# DiodeLadderFilter.net
KiCad netlist of a schematic drawn in Altium Designer
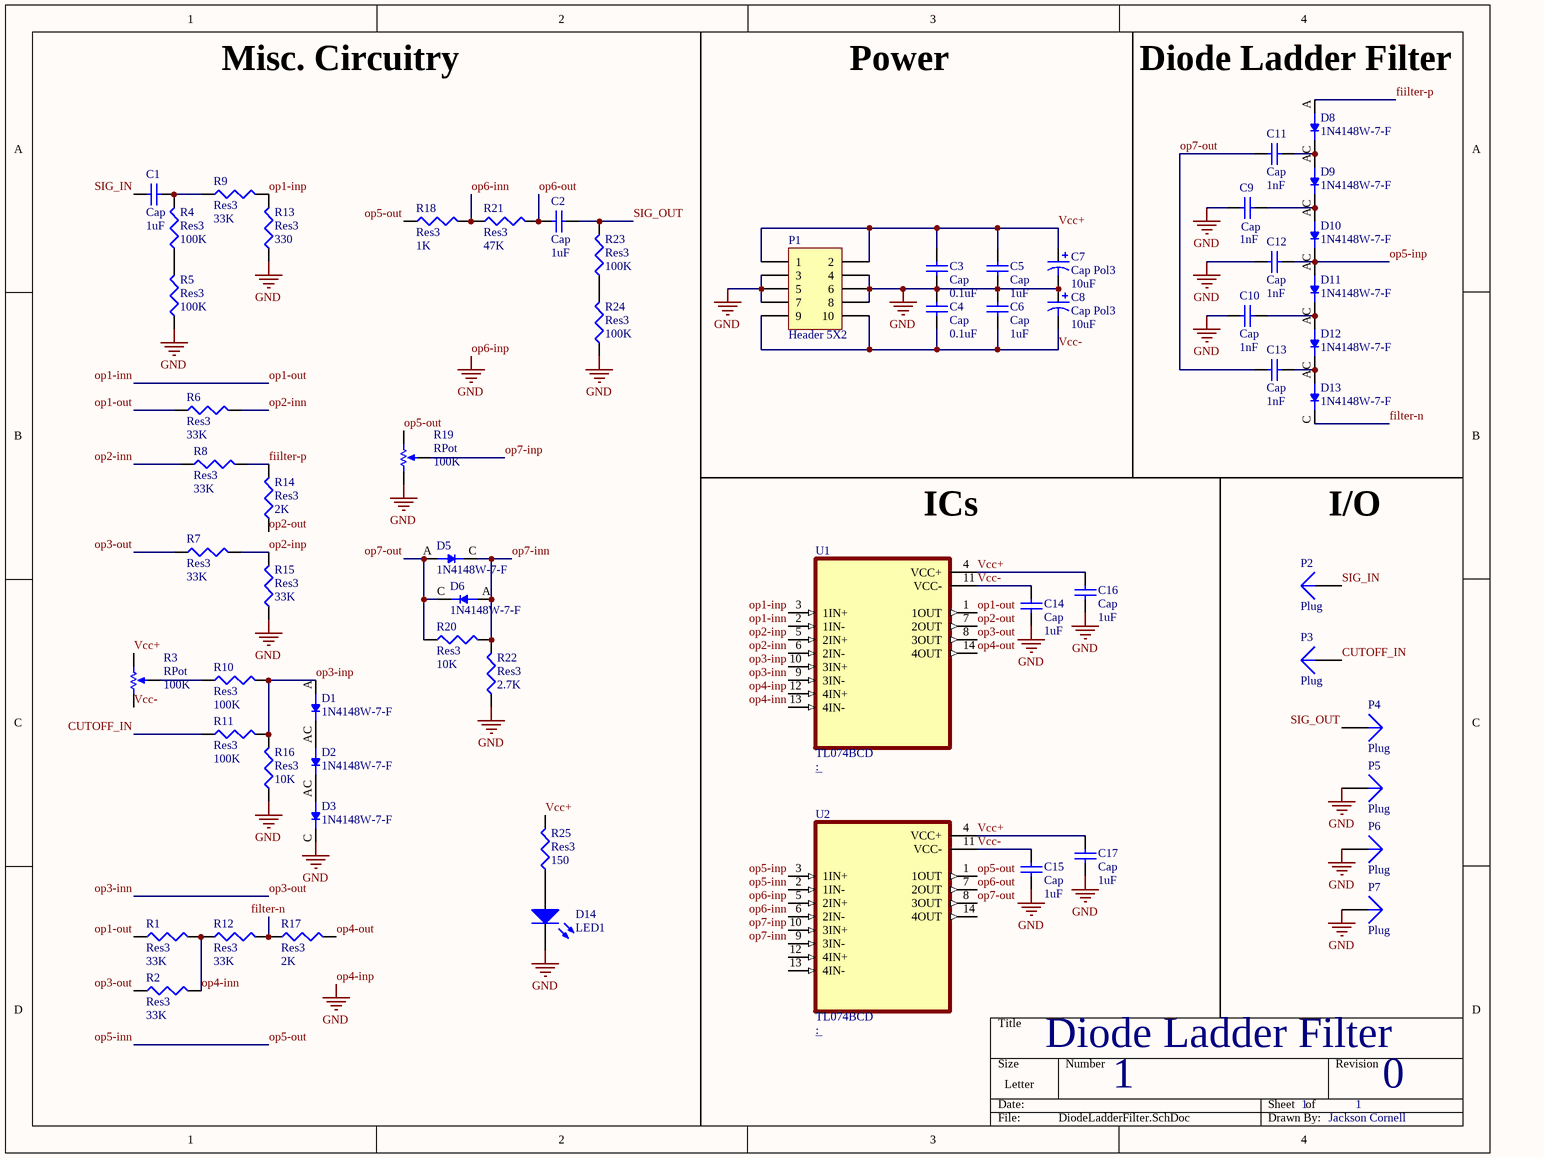
[diagram p0: DiodeLadderFilter.SchDoc]

(export (version "E")
  (design (tool "Eeschema 10.0.6"))
  (components
    (comp (ref "C1")
      (value "Cap")
      (footprint "CAPC1608X90")
      (description "Capacitor")
      (fields (field (name "ALTIUM_VALUE") "1uF") (field (name "PUBLISHER") "Altium Limited"))
      (libsource (lib "Miscellaneous Devices") (part "Cap"))
    )
    (comp (ref "C2")
      (value "Cap")
      (footprint "CAPC1608X90")
      (description "Capacitor")
      (fields (field (name "ALTIUM_VALUE") "1uF") (field (name "PUBLISHER") "Altium Limited"))
      (libsource (lib "Miscellaneous Devices") (part "Cap"))
    )
    (comp (ref "C3")
      (value "Cap")
      (footprint "CAPC1608X90")
      (description "Capacitor")
      (fields (field (name "ALTIUM_VALUE") "0.1uF") (field (name "PUBLISHER") "Altium Limited"))
      (libsource (lib "Miscellaneous Devices") (part "Cap"))
    )
    (comp (ref "C4")
      (value "Cap")
      (footprint "CAPC1608X90")
      (description "Capacitor")
      (fields (field (name "ALTIUM_VALUE") "0.1uF") (field (name "PUBLISHER") "Altium Limited"))
      (libsource (lib "Miscellaneous Devices") (part "Cap"))
    )
    (comp (ref "C5")
      (value "Cap")
      (footprint "CAPC1608X90")
      (description "Capacitor")
      (fields (field (name "ALTIUM_VALUE") "1uF") (field (name "PUBLISHER") "Altium Limited"))
      (libsource (lib "Miscellaneous Devices") (part "Cap"))
    )
    (comp (ref "C6")
      (value "Cap")
      (footprint "CAPC1608X90")
      (description "Capacitor")
      (fields (field (name "ALTIUM_VALUE") "1uF") (field (name "PUBLISHER") "Altium Limited"))
      (libsource (lib "Miscellaneous Devices") (part "Cap"))
    )
    (comp (ref "C7")
      (value "Cap Pol3")
      (footprint "2220")
      (description "Polarized Capacitor (Surface Mount)")
      (fields (field (name "ALTIUM_VALUE") "10uF") (field (name "PUBLISHER") "Altium Limited"))
      (libsource (lib "Miscellaneous Devices") (part "Cap Pol3"))
    )
    (comp (ref "C8")
      (value "Cap Pol3")
      (footprint "2220")
      (description "Polarized Capacitor (Surface Mount)")
      (fields (field (name "ALTIUM_VALUE") "10uF") (field (name "PUBLISHER") "Altium Limited"))
      (libsource (lib "Miscellaneous Devices") (part "Cap Pol3"))
    )
    (comp (ref "C9")
      (value "Cap")
      (footprint "CAPC1608X90")
      (description "Capacitor")
      (fields (field (name "ALTIUM_VALUE") "1nF") (field (name "PUBLISHER") "Altium Limited"))
      (libsource (lib "Miscellaneous Devices") (part "Cap"))
    )
    (comp (ref "C10")
      (value "Cap")
      (footprint "CAPC1608X90")
      (description "Capacitor")
      (fields (field (name "ALTIUM_VALUE") "1nF") (field (name "PUBLISHER") "Altium Limited"))
      (libsource (lib "Miscellaneous Devices") (part "Cap"))
    )
    (comp (ref "C11")
      (value "Cap")
      (footprint "CAPC1608X90")
      (description "Capacitor")
      (fields (field (name "ALTIUM_VALUE") "1nF") (field (name "PUBLISHER") "Altium Limited"))
      (libsource (lib "Miscellaneous Devices") (part "Cap"))
    )
    (comp (ref "C12")
      (value "Cap")
      (footprint "CAPC1608X90")
      (description "Capacitor")
      (fields (field (name "ALTIUM_VALUE") "1nF") (field (name "PUBLISHER") "Altium Limited"))
      (libsource (lib "Miscellaneous Devices") (part "Cap"))
    )
    (comp (ref "C13")
      (value "Cap")
      (footprint "CAPC1608X90")
      (description "Capacitor")
      (fields (field (name "ALTIUM_VALUE") "1nF") (field (name "PUBLISHER") "Altium Limited"))
      (libsource (lib "Miscellaneous Devices") (part "Cap"))
    )
    (comp (ref "C14")
      (value "Cap")
      (footprint "CAPC1608X90")
      (description "Capacitor")
      (fields (field (name "ALTIUM_VALUE") "1uF") (field (name "PUBLISHER") "Altium Limited"))
      (libsource (lib "Miscellaneous Devices") (part "Cap"))
    )
    (comp (ref "C15")
      (value "Cap")
      (footprint "CAPC1608X90")
      (description "Capacitor")
      (fields (field (name "ALTIUM_VALUE") "1uF") (field (name "PUBLISHER") "Altium Limited"))
      (libsource (lib "Miscellaneous Devices") (part "Cap"))
    )
    (comp (ref "C16")
      (value "Cap")
      (footprint "CAPC1608X90")
      (description "Capacitor")
      (fields (field (name "ALTIUM_VALUE") "1uF") (field (name "PUBLISHER") "Altium Limited"))
      (libsource (lib "Miscellaneous Devices") (part "Cap"))
    )
    (comp (ref "C17")
      (value "Cap")
      (footprint "CAPC1608X90")
      (description "Capacitor")
      (fields (field (name "ALTIUM_VALUE") "1uF") (field (name "PUBLISHER") "Altium Limited"))
      (libsource (lib "Miscellaneous Devices") (part "Cap"))
    )
    (comp (ref "D1")
      (value "1N4148W-7-F")
      (footprint "SODFL1608X70N")
      (description "Diode Standard 100V 300mA _DC_ Surface Mount SOD-123")
      (fields (field (name "MF") "Diodes Inc."))
      (libsource (lib "1N4148W-7-F") (part "1N4148W-7-F"))
    )
    (comp (ref "D2")
      (value "1N4148W-7-F")
      (footprint "SODFL1608X70N")
      (description "Diode Standard 100V 300mA _DC_ Surface Mount SOD-123")
      (fields (field (name "MF") "Diodes Inc."))
      (libsource (lib "1N4148W-7-F") (part "1N4148W-7-F"))
    )
    (comp (ref "D3")
      (value "1N4148W-7-F")
      (footprint "SODFL1608X70N")
      (description "Diode Standard 100V 300mA _DC_ Surface Mount SOD-123")
      (fields (field (name "MF") "Diodes Inc."))
      (libsource (lib "1N4148W-7-F") (part "1N4148W-7-F"))
    )
    (comp (ref "D5")
      (value "1N4148W-7-F")
      (footprint "SODFL1608X70N")
      (description "Diode Standard 100V 300mA _DC_ Surface Mount SOD-123")
      (fields (field (name "MF") "Diodes Inc."))
      (libsource (lib "1N4148W-7-F") (part "1N4148W-7-F"))
    )
    (comp (ref "D6")
      (value "1N4148W-7-F")
      (footprint "SODFL1608X70N")
      (description "Diode Standard 100V 300mA _DC_ Surface Mount SOD-123")
      (fields (field (name "MF") "Diodes Inc."))
      (libsource (lib "1N4148W-7-F") (part "1N4148W-7-F"))
    )
    (comp (ref "D8")
      (value "1N4148W-7-F")
      (footprint "SODFL1608X70N")
      (description "Diode Standard 100V 300mA _DC_ Surface Mount SOD-123")
      (fields (field (name "MF") "Diodes Inc."))
      (libsource (lib "1N4148W-7-F") (part "1N4148W-7-F"))
    )
    (comp (ref "D9")
      (value "1N4148W-7-F")
      (footprint "SODFL1608X70N")
      (description "Diode Standard 100V 300mA _DC_ Surface Mount SOD-123")
      (fields (field (name "MF") "Diodes Inc."))
      (libsource (lib "1N4148W-7-F") (part "1N4148W-7-F"))
    )
    (comp (ref "D10")
      (value "1N4148W-7-F")
      (footprint "SODFL1608X70N")
      (description "Diode Standard 100V 300mA _DC_ Surface Mount SOD-123")
      (fields (field (name "MF") "Diodes Inc."))
      (libsource (lib "1N4148W-7-F") (part "1N4148W-7-F"))
    )
    (comp (ref "D11")
      (value "1N4148W-7-F")
      (footprint "SODFL1608X70N")
      (description "Diode Standard 100V 300mA _DC_ Surface Mount SOD-123")
      (fields (field (name "MF") "Diodes Inc."))
      (libsource (lib "1N4148W-7-F") (part "1N4148W-7-F"))
    )
    (comp (ref "D12")
      (value "1N4148W-7-F")
      (footprint "SODFL1608X70N")
      (description "Diode Standard 100V 300mA _DC_ Surface Mount SOD-123")
      (fields (field (name "MF") "Diodes Inc."))
      (libsource (lib "1N4148W-7-F") (part "1N4148W-7-F"))
    )
    (comp (ref "D13")
      (value "1N4148W-7-F")
      (footprint "SODFL1608X70N")
      (description "Diode Standard 100V 300mA _DC_ Surface Mount SOD-123")
      (fields (field (name "MF") "Diodes Inc."))
      (libsource (lib "1N4148W-7-F") (part "1N4148W-7-F"))
    )
    (comp (ref "D14")
      (value "LED1")
      (footprint "LED-1")
      (description "Typical RED GaAs LED")
      (fields (field (name "PUBLISHER") "Altium Limited"))
      (libsource (lib "Miscellaneous Devices") (part "LED1"))
    )
    (comp (ref "P1")
      (value "Header 5X2")
      (footprint "HDR2X5")
      (description "Header, 5-Pin, Dual row")
      (fields (field (name "PUBLISHER") "Altium Limited"))
      (libsource (lib "Miscellaneous Connectors") (part "Header 5X2"))
    )
    (comp (ref "P2")
      (value "Plug")
      (footprint "PIN1")
      (fields (field (name "PUBLISHER") "Altium Limited"))
      (libsource (lib "Miscellaneous Connectors") (part "Plug"))
    )
    (comp (ref "P3")
      (value "Plug")
      (footprint "PIN1")
      (fields (field (name "PUBLISHER") "Altium Limited"))
      (libsource (lib "Miscellaneous Connectors") (part "Plug"))
    )
    (comp (ref "P4")
      (value "Plug")
      (footprint "PIN1")
      (fields (field (name "PUBLISHER") "Altium Limited"))
      (libsource (lib "Miscellaneous Connectors") (part "Plug"))
    )
    (comp (ref "P5")
      (value "Plug")
      (footprint "PIN1")
      (fields (field (name "PUBLISHER") "Altium Limited"))
      (libsource (lib "Miscellaneous Connectors") (part "Plug"))
    )
    (comp (ref "P6")
      (value "Plug")
      (footprint "PIN1")
      (fields (field (name "PUBLISHER") "Altium Limited"))
      (libsource (lib "Miscellaneous Connectors") (part "Plug"))
    )
    (comp (ref "P7")
      (value "Plug")
      (footprint "PIN1")
      (fields (field (name "PUBLISHER") "Altium Limited"))
      (libsource (lib "Miscellaneous Connectors") (part "Plug"))
    )
    (comp (ref "R1")
      (value "Res3")
      (footprint "J1-0603")
      (description "Resistor")
      (fields (field (name "ALTIUM_VALUE") "33K") (field (name "PUBLISHER") "Altium Limited"))
      (libsource (lib "Miscellaneous Devices") (part "Res3"))
    )
    (comp (ref "R2")
      (value "Res3")
      (footprint "J1-0603")
      (description "Resistor")
      (fields (field (name "ALTIUM_VALUE") "33K") (field (name "PUBLISHER") "Altium Limited"))
      (libsource (lib "Miscellaneous Devices") (part "Res3"))
    )
    (comp (ref "R3")
      (value "RPot")
      (footprint "VR5")
      (description "Potentiometer")
      (fields (field (name "ALTIUM_VALUE") "100K") (field (name "PUBLISHER") "Altium Limited"))
      (libsource (lib "Miscellaneous Devices") (part "RPot"))
    )
    (comp (ref "R4")
      (value "Res3")
      (footprint "J1-0603")
      (description "Resistor")
      (fields (field (name "ALTIUM_VALUE") "100K") (field (name "PUBLISHER") "Altium Limited"))
      (libsource (lib "Miscellaneous Devices") (part "Res3"))
    )
    (comp (ref "R5")
      (value "Res3")
      (footprint "J1-0603")
      (description "Resistor")
      (fields (field (name "ALTIUM_VALUE") "100K") (field (name "PUBLISHER") "Altium Limited"))
      (libsource (lib "Miscellaneous Devices") (part "Res3"))
    )
    (comp (ref "R6")
      (value "Res3")
      (footprint "J1-0603")
      (description "Resistor")
      (fields (field (name "ALTIUM_VALUE") "33K") (field (name "PUBLISHER") "Altium Limited"))
      (libsource (lib "Miscellaneous Devices") (part "Res3"))
    )
    (comp (ref "R7")
      (value "Res3")
      (footprint "J1-0603")
      (description "Resistor")
      (fields (field (name "ALTIUM_VALUE") "33K") (field (name "PUBLISHER") "Altium Limited"))
      (libsource (lib "Miscellaneous Devices") (part "Res3"))
    )
    (comp (ref "R8")
      (value "Res3")
      (footprint "J1-0603")
      (description "Resistor")
      (fields (field (name "ALTIUM_VALUE") "33K") (field (name "PUBLISHER") "Altium Limited"))
      (libsource (lib "Miscellaneous Devices") (part "Res3"))
    )
    (comp (ref "R9")
      (value "Res3")
      (footprint "J1-0603")
      (description "Resistor")
      (fields (field (name "ALTIUM_VALUE") "33K") (field (name "PUBLISHER") "Altium Limited"))
      (libsource (lib "Miscellaneous Devices") (part "Res3"))
    )
    (comp (ref "R10")
      (value "Res3")
      (footprint "J1-0603")
      (description "Resistor")
      (fields (field (name "ALTIUM_VALUE") "100K") (field (name "PUBLISHER") "Altium Limited"))
      (libsource (lib "Miscellaneous Devices") (part "Res3"))
    )
    (comp (ref "R11")
      (value "Res3")
      (footprint "J1-0603")
      (description "Resistor")
      (fields (field (name "ALTIUM_VALUE") "100K") (field (name "PUBLISHER") "Altium Limited"))
      (libsource (lib "Miscellaneous Devices") (part "Res3"))
    )
    (comp (ref "R12")
      (value "Res3")
      (footprint "J1-0603")
      (description "Resistor")
      (fields (field (name "ALTIUM_VALUE") "33K") (field (name "PUBLISHER") "Altium Limited"))
      (libsource (lib "Miscellaneous Devices") (part "Res3"))
    )
    (comp (ref "R13")
      (value "Res3")
      (footprint "J1-0603")
      (description "Resistor")
      (fields (field (name "ALTIUM_VALUE") "330") (field (name "PUBLISHER") "Altium Limited"))
      (libsource (lib "Miscellaneous Devices") (part "Res3"))
    )
    (comp (ref "R14")
      (value "Res3")
      (footprint "J1-0603")
      (description "Resistor")
      (fields (field (name "ALTIUM_VALUE") "2K") (field (name "PUBLISHER") "Altium Limited"))
      (libsource (lib "Miscellaneous Devices") (part "Res3"))
    )
    (comp (ref "R15")
      (value "Res3")
      (footprint "J1-0603")
      (description "Resistor")
      (fields (field (name "ALTIUM_VALUE") "33K") (field (name "PUBLISHER") "Altium Limited"))
      (libsource (lib "Miscellaneous Devices") (part "Res3"))
    )
    (comp (ref "R16")
      (value "Res3")
      (footprint "J1-0603")
      (description "Resistor")
      (fields (field (name "ALTIUM_VALUE") "10K") (field (name "PUBLISHER") "Altium Limited"))
      (libsource (lib "Miscellaneous Devices") (part "Res3"))
    )
    (comp (ref "R17")
      (value "Res3")
      (footprint "J1-0603")
      (description "Resistor")
      (fields (field (name "ALTIUM_VALUE") "2K") (field (name "PUBLISHER") "Altium Limited"))
      (libsource (lib "Miscellaneous Devices") (part "Res3"))
    )
    (comp (ref "R18")
      (value "Res3")
      (footprint "J1-0603")
      (description "Resistor")
      (fields (field (name "ALTIUM_VALUE") "1K") (field (name "PUBLISHER") "Altium Limited"))
      (libsource (lib "Miscellaneous Devices") (part "Res3"))
    )
    (comp (ref "R19")
      (value "RPot")
      (footprint "VR5")
      (description "Potentiometer")
      (fields (field (name "ALTIUM_VALUE") "100K") (field (name "PUBLISHER") "Altium Limited"))
      (libsource (lib "Miscellaneous Devices") (part "RPot"))
    )
    (comp (ref "R20")
      (value "Res3")
      (footprint "J1-0603")
      (description "Resistor")
      (fields (field (name "ALTIUM_VALUE") "10K") (field (name "PUBLISHER") "Altium Limited"))
      (libsource (lib "Miscellaneous Devices") (part "Res3"))
    )
    (comp (ref "R21")
      (value "Res3")
      (footprint "J1-0603")
      (description "Resistor")
      (fields (field (name "ALTIUM_VALUE") "47K") (field (name "PUBLISHER") "Altium Limited"))
      (libsource (lib "Miscellaneous Devices") (part "Res3"))
    )
    (comp (ref "R22")
      (value "Res3")
      (footprint "J1-0603")
      (description "Resistor")
      (fields (field (name "ALTIUM_VALUE") "2.7K") (field (name "PUBLISHER") "Altium Limited"))
      (libsource (lib "Miscellaneous Devices") (part "Res3"))
    )
    (comp (ref "R23")
      (value "Res3")
      (footprint "J1-0603")
      (description "Resistor")
      (fields (field (name "ALTIUM_VALUE") "100K") (field (name "PUBLISHER") "Altium Limited"))
      (libsource (lib "Miscellaneous Devices") (part "Res3"))
    )
    (comp (ref "R24")
      (value "Res3")
      (footprint "J1-0603")
      (description "Resistor")
      (fields (field (name "ALTIUM_VALUE") "100K") (field (name "PUBLISHER") "Altium Limited"))
      (libsource (lib "Miscellaneous Devices") (part "Res3"))
    )
    (comp (ref "R25")
      (value "Res3")
      (footprint "J1-0603")
      (description "Resistor")
      (fields (field (name "ALTIUM_VALUE") "150") (field (name "PUBLISHER") "Altium Limited"))
      (libsource (lib "Miscellaneous Devices") (part "Res3"))
    )
    (comp (ref "U1")
      (value "TL074BCD")
      (footprint "SOIC127P600X175-14N")
      (description "Quad low-noise JFET-input low offset operational amplifier 14-SOIC 0 to 70")
      (fields (field (name "MF") "Texas Instruments"))
      (libsource (lib "TL074BCD") (part "TL074BCD"))
    )
    (comp (ref "U2")
      (value "TL074BCD")
      (footprint "SOIC127P600X175-14N")
      (description "Quad low-noise JFET-input low offset operational amplifier 14-SOIC 0 to 70")
      (fields (field (name "MF") "Texas Instruments"))
      (libsource (lib "TL074BCD") (part "TL074BCD"))
    )
  )
  (nets
    (net (code "1") (name "/CUTOFF_IN") (class "Default")
      (node (ref "P3") (pin "1") (pinfunction "1_1") (pintype "passive"))
      (node (ref "R11") (pin "1") (pinfunction "1_1") (pintype "passive"))
    )
    (net (code "2") (name "/SIG_IN") (class "Default")
      (node (ref "C1") (pin "1") (pinfunction "1_1") (pintype "passive"))
      (node (ref "P2") (pin "1") (pinfunction "1_1") (pintype "passive"))
    )
    (net (code "3") (name "/SIG_OUT") (class "Default")
      (node (ref "C2") (pin "2") (pinfunction "2_2") (pintype "passive"))
      (node (ref "P4") (pin "1") (pinfunction "1_1") (pintype "passive"))
      (node (ref "R23") (pin "2") (pinfunction "2_2") (pintype "passive"))
    )
    (net (code "4") (name "/Vcc+") (class "Default")
      (node (ref "C16") (pin "2") (pinfunction "2_2") (pintype "passive"))
      (node (ref "C17") (pin "2") (pinfunction "2_2") (pintype "passive"))
      (node (ref "C3") (pin "2") (pinfunction "2_2") (pintype "passive"))
      (node (ref "C5") (pin "2") (pinfunction "2_2") (pintype "passive"))
      (node (ref "C7") (pin "1") (pinfunction "1_1") (pintype "passive"))
      (node (ref "P1") (pin "1") (pinfunction "1_1") (pintype "passive"))
      (node (ref "P1") (pin "2") (pinfunction "2_2") (pintype "passive"))
      (node (ref "R25") (pin "2") (pinfunction "2_2") (pintype "passive"))
      (node (ref "R3") (pin "2") (pinfunction "BOT_2") (pintype "passive"))
      (node (ref "U1") (pin "4") (pinfunction "VCC+_4") (pintype "power_in"))
      (node (ref "U2") (pin "4") (pinfunction "VCC+_4") (pintype "power_in"))
    )
    (net (code "5") (name "/Vcc-") (class "Default")
      (node (ref "C14") (pin "2") (pinfunction "2_2") (pintype "passive"))
      (node (ref "C15") (pin "2") (pinfunction "2_2") (pintype "passive"))
      (node (ref "C4") (pin "1") (pinfunction "1_1") (pintype "passive"))
      (node (ref "C6") (pin "1") (pinfunction "1_1") (pintype "passive"))
      (node (ref "C8") (pin "2") (pinfunction "2_2") (pintype "passive"))
      (node (ref "P1") (pin "10") (pinfunction "10_10") (pintype "passive"))
      (node (ref "P1") (pin "9") (pinfunction "9_9") (pintype "passive"))
      (node (ref "R3") (pin "1") (pinfunction "TOP_1") (pintype "passive"))
      (node (ref "U1") (pin "11") (pinfunction "VCC-_11") (pintype "power_in"))
      (node (ref "U2") (pin "11") (pinfunction "VCC-_11") (pintype "power_in"))
    )
    (net (code "6") (name "/fiilter-p") (class "Default")
      (node (ref "D8") (pin "A") (pinfunction "A_A") (pintype "passive"))
      (node (ref "R14") (pin "2") (pinfunction "2_2") (pintype "passive"))
      (node (ref "R8") (pin "2") (pinfunction "2_2") (pintype "passive"))
    )
    (net (code "7") (name "/filter-n") (class "Default")
      (node (ref "D13") (pin "C") (pinfunction "K_C") (pintype "passive"))
      (node (ref "R12") (pin "2") (pinfunction "2_2") (pintype "passive"))
      (node (ref "R17") (pin "1") (pinfunction "1_1") (pintype "passive"))
    )
    (net (code "8") (name "/op1-inn") (class "Default")
      (node (ref "R1") (pin "1") (pinfunction "1_1") (pintype "passive"))
      (node (ref "R6") (pin "1") (pinfunction "1_1") (pintype "passive"))
      (node (ref "U1") (pin "1") (pinfunction "1OUT_1") (pintype "output"))
      (node (ref "U1") (pin "2") (pinfunction "1IN-_2") (pintype "input"))
    )
    (net (code "9") (name "/op1-inp") (class "Default")
      (node (ref "R13") (pin "2") (pinfunction "2_2") (pintype "passive"))
      (node (ref "R9") (pin "2") (pinfunction "2_2") (pintype "passive"))
      (node (ref "U1") (pin "3") (pinfunction "1IN+_3") (pintype "input"))
    )
    (net (code "10") (name "/op2-inn") (class "Default")
      (node (ref "R6") (pin "2") (pinfunction "2_2") (pintype "passive"))
      (node (ref "R8") (pin "1") (pinfunction "1_1") (pintype "passive"))
      (node (ref "U1") (pin "6") (pinfunction "2IN-_6") (pintype "input"))
    )
    (net (code "11") (name "/op2-inp") (class "Default")
      (node (ref "R15") (pin "2") (pinfunction "2_2") (pintype "passive"))
      (node (ref "R7") (pin "2") (pinfunction "2_2") (pintype "passive"))
      (node (ref "U1") (pin "5") (pinfunction "2IN+_5") (pintype "input"))
    )
    (net (code "12") (name "/op2-out") (class "Default")
      (node (ref "R14") (pin "1") (pinfunction "1_1") (pintype "passive"))
      (node (ref "U1") (pin "7") (pinfunction "2OUT_7") (pintype "output"))
    )
    (net (code "13") (name "/op3-inn") (class "Default")
      (node (ref "R2") (pin "1") (pinfunction "1_1") (pintype "passive"))
      (node (ref "R7") (pin "1") (pinfunction "1_1") (pintype "passive"))
      (node (ref "U1") (pin "8") (pinfunction "3OUT_8") (pintype "output"))
      (node (ref "U1") (pin "9") (pinfunction "3IN-_9") (pintype "input"))
    )
    (net (code "14") (name "/op3-inp") (class "Default")
      (node (ref "D1") (pin "A") (pinfunction "A_A") (pintype "passive"))
      (node (ref "R10") (pin "2") (pinfunction "2_2") (pintype "passive"))
      (node (ref "R11") (pin "2") (pinfunction "2_2") (pintype "passive"))
      (node (ref "R16") (pin "2") (pinfunction "2_2") (pintype "passive"))
      (node (ref "U1") (pin "10") (pinfunction "3IN+_10") (pintype "input"))
    )
    (net (code "15") (name "/op4-inn") (class "Default")
      (node (ref "R1") (pin "2") (pinfunction "2_2") (pintype "passive"))
      (node (ref "R12") (pin "1") (pinfunction "1_1") (pintype "passive"))
      (node (ref "R2") (pin "2") (pinfunction "2_2") (pintype "passive"))
      (node (ref "U1") (pin "13") (pinfunction "4IN-_13") (pintype "input"))
    )
    (net (code "16") (name "/op4-out") (class "Default")
      (node (ref "R17") (pin "2") (pinfunction "2_2") (pintype "passive"))
      (node (ref "U1") (pin "14") (pinfunction "4OUT_14") (pintype "output"))
    )
    (net (code "17") (name "/op5-inn") (class "Default")
      (node (ref "R18") (pin "1") (pinfunction "1_1") (pintype "passive"))
      (node (ref "R19") (pin "2") (pinfunction "BOT_2") (pintype "passive"))
      (node (ref "U2") (pin "1") (pinfunction "1OUT_1") (pintype "output"))
      (node (ref "U2") (pin "2") (pinfunction "1IN-_2") (pintype "input"))
    )
    (net (code "18") (name "/op5-inp") (class "Default")
      (node (ref "C12") (pin "2") (pinfunction "2_2") (pintype "passive"))
      (node (ref "D10") (pin "C") (pinfunction "K_C") (pintype "passive"))
      (node (ref "D11") (pin "A") (pinfunction "A_A") (pintype "passive"))
      (node (ref "U2") (pin "3") (pinfunction "1IN+_3") (pintype "input"))
    )
    (net (code "19") (name "/op6-inn") (class "Default")
      (node (ref "R18") (pin "2") (pinfunction "2_2") (pintype "passive"))
      (node (ref "R21") (pin "1") (pinfunction "1_1") (pintype "passive"))
      (node (ref "U2") (pin "6") (pinfunction "2IN-_6") (pintype "input"))
    )
    (net (code "20") (name "/op6-out") (class "Default")
      (node (ref "C2") (pin "1") (pinfunction "1_1") (pintype "passive"))
      (node (ref "R21") (pin "2") (pinfunction "2_2") (pintype "passive"))
      (node (ref "U2") (pin "7") (pinfunction "2OUT_7") (pintype "output"))
    )
    (net (code "21") (name "/op7-inn") (class "Default")
      (node (ref "D5") (pin "C") (pinfunction "K_C") (pintype "passive"))
      (node (ref "D6") (pin "A") (pinfunction "A_A") (pintype "passive"))
      (node (ref "R20") (pin "2") (pinfunction "2_2") (pintype "passive"))
      (node (ref "R22") (pin "2") (pinfunction "2_2") (pintype "passive"))
      (node (ref "U2") (pin "9") (pinfunction "3IN-_9") (pintype "input"))
    )
    (net (code "22") (name "/op7-inp") (class "Default")
      (node (ref "R19") (pin "3") (pinfunction "TAP_3") (pintype "passive"))
      (node (ref "U2") (pin "10") (pinfunction "3IN+_10") (pintype "input"))
    )
    (net (code "23") (name "/op7-out") (class "Default")
      (node (ref "C11") (pin "1") (pinfunction "1_1") (pintype "passive"))
      (node (ref "C13") (pin "1") (pinfunction "1_1") (pintype "passive"))
      (node (ref "D5") (pin "A") (pinfunction "A_A") (pintype "passive"))
      (node (ref "D6") (pin "C") (pinfunction "K_C") (pintype "passive"))
      (node (ref "R20") (pin "1") (pinfunction "1_1") (pintype "passive"))
      (node (ref "U2") (pin "8") (pinfunction "3OUT_8") (pintype "output"))
    )
    (net (code "24") (name "GND") (class "Default")
      (node (ref "C10") (pin "1") (pinfunction "1_1") (pintype "passive"))
      (node (ref "C12") (pin "1") (pinfunction "1_1") (pintype "passive"))
      (node (ref "C14") (pin "1") (pinfunction "1_1") (pintype "passive"))
      (node (ref "C15") (pin "1") (pinfunction "1_1") (pintype "passive"))
      (node (ref "C16") (pin "1") (pinfunction "1_1") (pintype "passive"))
      (node (ref "C17") (pin "1") (pinfunction "1_1") (pintype "passive"))
      (node (ref "C3") (pin "1") (pinfunction "1_1") (pintype "passive"))
      (node (ref "C4") (pin "2") (pinfunction "2_2") (pintype "passive"))
      (node (ref "C5") (pin "1") (pinfunction "1_1") (pintype "passive"))
      (node (ref "C6") (pin "2") (pinfunction "2_2") (pintype "passive"))
      (node (ref "C7") (pin "2") (pinfunction "2_2") (pintype "passive"))
      (node (ref "C8") (pin "1") (pinfunction "1_1") (pintype "passive"))
      (node (ref "C9") (pin "1") (pinfunction "1_1") (pintype "passive"))
      (node (ref "D14") (pin "2") (pinfunction "K_2") (pintype "passive"))
      (node (ref "D3") (pin "C") (pinfunction "K_C") (pintype "passive"))
      (node (ref "P1") (pin "3") (pinfunction "3_3") (pintype "passive"))
      (node (ref "P1") (pin "4") (pinfunction "4_4") (pintype "passive"))
      (node (ref "P1") (pin "5") (pinfunction "5_5") (pintype "passive"))
      (node (ref "P1") (pin "6") (pinfunction "6_6") (pintype "passive"))
      (node (ref "P1") (pin "7") (pinfunction "7_7") (pintype "passive"))
      (node (ref "P1") (pin "8") (pinfunction "8_8") (pintype "passive"))
      (node (ref "P5") (pin "1") (pinfunction "1_1") (pintype "passive"))
      (node (ref "P6") (pin "1") (pinfunction "1_1") (pintype "passive"))
      (node (ref "P7") (pin "1") (pinfunction "1_1") (pintype "passive"))
      (node (ref "R13") (pin "1") (pinfunction "1_1") (pintype "passive"))
      (node (ref "R15") (pin "1") (pinfunction "1_1") (pintype "passive"))
      (node (ref "R16") (pin "1") (pinfunction "1_1") (pintype "passive"))
      (node (ref "R19") (pin "1") (pinfunction "TOP_1") (pintype "passive"))
      (node (ref "R22") (pin "1") (pinfunction "1_1") (pintype "passive"))
      (node (ref "R24") (pin "1") (pinfunction "1_1") (pintype "passive"))
      (node (ref "R5") (pin "1") (pinfunction "1_1") (pintype "passive"))
      (node (ref "U1") (pin "12") (pinfunction "4IN+_12") (pintype "input"))
      (node (ref "U2") (pin "5") (pinfunction "2IN+_5") (pintype "input"))
    )
    (net (code "25") (name "Net-(C1-Pad2)") (class "Default")
      (node (ref "C1") (pin "2") (pinfunction "2_2") (pintype "passive"))
      (node (ref "R4") (pin "2") (pinfunction "2_2") (pintype "passive"))
      (node (ref "R9") (pin "1") (pinfunction "1_1") (pintype "passive"))
    )
    (net (code "26") (name "Net-(D1-K)") (class "Default")
      (node (ref "D1") (pin "C") (pinfunction "K_C") (pintype "passive"))
      (node (ref "D2") (pin "A") (pinfunction "A_A") (pintype "passive"))
    )
    (net (code "27") (name "Net-(D2-K)") (class "Default")
      (node (ref "D2") (pin "C") (pinfunction "K_C") (pintype "passive"))
      (node (ref "D3") (pin "A") (pinfunction "A_A") (pintype "passive"))
    )
    (net (code "28") (name "Net-(D8-K)") (class "Default")
      (node (ref "C11") (pin "2") (pinfunction "2_2") (pintype "passive"))
      (node (ref "D8") (pin "C") (pinfunction "K_C") (pintype "passive"))
      (node (ref "D9") (pin "A") (pinfunction "A_A") (pintype "passive"))
    )
    (net (code "29") (name "Net-(D9-K)") (class "Default")
      (node (ref "C9") (pin "2") (pinfunction "2_2") (pintype "passive"))
      (node (ref "D10") (pin "A") (pinfunction "A_A") (pintype "passive"))
      (node (ref "D9") (pin "C") (pinfunction "K_C") (pintype "passive"))
    )
    (net (code "30") (name "Net-(D11-K)") (class "Default")
      (node (ref "C10") (pin "2") (pinfunction "2_2") (pintype "passive"))
      (node (ref "D11") (pin "C") (pinfunction "K_C") (pintype "passive"))
      (node (ref "D12") (pin "A") (pinfunction "A_A") (pintype "passive"))
    )
    (net (code "31") (name "Net-(D12-K)") (class "Default")
      (node (ref "C13") (pin "2") (pinfunction "2_2") (pintype "passive"))
      (node (ref "D12") (pin "C") (pinfunction "K_C") (pintype "passive"))
      (node (ref "D13") (pin "A") (pinfunction "A_A") (pintype "passive"))
    )
    (net (code "32") (name "Net-(D14-A)") (class "Default")
      (node (ref "D14") (pin "1") (pinfunction "A_1") (pintype "passive"))
      (node (ref "R25") (pin "1") (pinfunction "1_1") (pintype "passive"))
    )
    (net (code "33") (name "Net-(R3-TAP)") (class "Default")
      (node (ref "R10") (pin "1") (pinfunction "1_1") (pintype "passive"))
      (node (ref "R3") (pin "3") (pinfunction "TAP_3") (pintype "passive"))
    )
    (net (code "34") (name "Net-(R4-Pad1)") (class "Default")
      (node (ref "R4") (pin "1") (pinfunction "1_1") (pintype "passive"))
      (node (ref "R5") (pin "2") (pinfunction "2_2") (pintype "passive"))
    )
    (net (code "35") (name "Net-(R23-Pad1)") (class "Default")
      (node (ref "R23") (pin "1") (pinfunction "1_1") (pintype "passive"))
      (node (ref "R24") (pin "2") (pinfunction "2_2") (pintype "passive"))
    )
    (net (code "36") (name "unconnected-(U2-4IN+-Pad12)") (class "Default")
      (node (ref "U2") (pin "12") (pinfunction "4IN+_12") (pintype "input"))
    )
    (net (code "37") (name "unconnected-(U2-4IN--Pad13)") (class "Default")
      (node (ref "U2") (pin "13") (pinfunction "4IN-_13") (pintype "input"))
    )
    (net (code "38") (name "unconnected-(U2-4OUT-Pad14)") (class "Default")
      (node (ref "U2") (pin "14") (pinfunction "4OUT_14") (pintype "output"))
    )
  )
)
